# ADS1158.net
KiCad netlist of a schematic drawn in Altium Designer
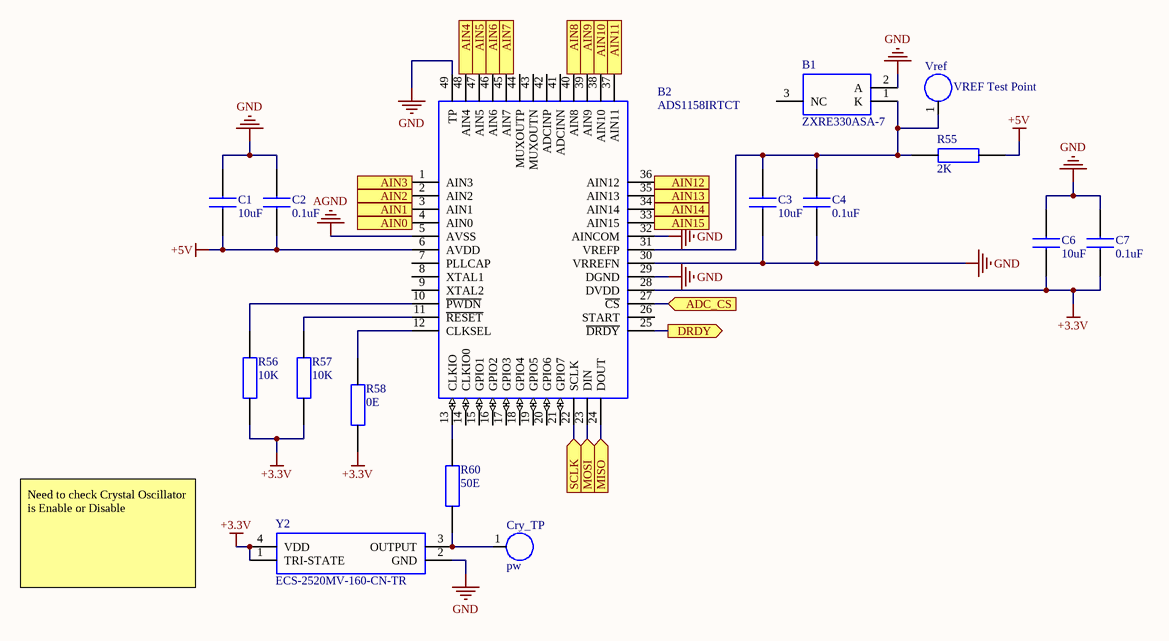
[diagram p0: ADS1158.SchDoc]

(export (version "E")
  (design (tool "Eeschema 10.0.6"))
  (components
    (comp (ref "B1")
      (value "ZXRE330ASA-7")
      (footprint "SOT96P240X110-3N")
      (description "Diodes Inc ZXRE330ASA-7, Shunt Precision Voltage Reference 3.3V, +/-0.5%, 3-Pin SOT-23")
      (fields (field (name "MOUSER PART NUMBER") "621-ZXRE330ASA-7"))
      (libsource (lib "ZXRE330ASA-7") (part "ZXRE330ASA-7"))
    )
    (comp (ref "B2")
      (value "ADS1158IRTCT")
      (footprint "QFN-48")
      (description "16-Bit, 125kSPS, 16-Ch Delta-Sigma ADC w/ Fast Channel Scan & Automatic Sequencer")
      (fields (field (name "MOUSER PART NUMBER") "595-ADS1158IRTCT"))
      (libsource (lib "ADS1158IRTCT") (part "ADS1158IRTCT"))
    )
    (comp (ref "C1")
      (value "10uF")
      (footprint "CAPC1608X80N")
      (description "TDK - C1608X5R1A106K080AC - CAP, MLCC, X5R, 10UF, 10V, 0603")
      (fields
        (field (name "MANUFACTURER_PART_NUMBER") "C1608X5R1A106K080AC")
        (field (name "MOUSER PART NUMBER") "810-C1608X5R1A106K")
      )
      (libsource (lib "10uF_0603") (part "C1608X5R1A106K080AC"))
    )
    (comp (ref "C2")
      (value "0.1uF")
      (footprint "CAPC1005X55N")
      (description "Multilayer Ceramic Capacitors MLCC - SMD/SMT 16V 0.1uF X7R 0402 20%")
      (fields
        (field (name "MANUFACTURER_PART_NUMBER") "C0402C104M4RECTU")
        (field (name "MOUSER PART NUMBER") "80-C0402C104M4RECTU")
      )
      (libsource (lib "0.1uF_0402") (part "C0402C104M4RECTU"))
    )
    (comp (ref "C3")
      (value "10uF")
      (footprint "CAPC1608X80N")
      (description "TDK - C1608X5R1A106K080AC - CAP, MLCC, X5R, 10UF, 10V, 0603")
      (fields
        (field (name "MANUFACTURER_PART_NUMBER") "C1608X5R1A106K080AC")
        (field (name "MOUSER PART NUMBER") "810-C1608X5R1A106K")
      )
      (libsource (lib "10uF_0603") (part "C1608X5R1A106K080AC"))
    )
    (comp (ref "C4")
      (value "0.1uF")
      (footprint "CAPC1005X55N")
      (description "Multilayer Ceramic Capacitors MLCC - SMD/SMT 16V 0.1uF X7R 0402 20%")
      (fields
        (field (name "MANUFACTURER_PART_NUMBER") "C0402C104M4RECTU")
        (field (name "MOUSER PART NUMBER") "80-C0402C104M4RECTU")
      )
      (libsource (lib "0.1uF_0402") (part "C0402C104M4RECTU"))
    )
    (comp (ref "C6")
      (value "10uF")
      (footprint "CAPC1608X80N")
      (description "TDK - C1608X5R1A106K080AC - CAP, MLCC, X5R, 10UF, 10V, 0603")
      (fields
        (field (name "MANUFACTURER_PART_NUMBER") "C1608X5R1A106K080AC")
        (field (name "MOUSER PART NUMBER") "810-C1608X5R1A106K")
      )
      (libsource (lib "10uF_0603") (part "C1608X5R1A106K080AC"))
    )
    (comp (ref "C7")
      (value "0.1uF")
      (footprint "CAPC1005X55N")
      (description "Multilayer Ceramic Capacitors MLCC - SMD/SMT 16V 0.1uF X7R 0402 20%")
      (fields
        (field (name "MANUFACTURER_PART_NUMBER") "C0402C104M4RECTU")
        (field (name "MOUSER PART NUMBER") "80-C0402C104M4RECTU")
      )
      (libsource (lib "0.1uF_0402") (part "C0402C104M4RECTU"))
    )
    (comp (ref "Cry_TP")
      (value "pw")
      (footprint "Test Points")
      (libsource (lib "CV-R-BAP_V2.1.5") (part "Test Points"))
    )
    (comp (ref "R55")
      (value "2K")
      (footprint "RESC1005X40N")
      (description "RESISTOR, 0402 2K Ohms +/-5% 1/16 W")
      (fields
        (field (name "MANUFACTURER_PART_NUMBER") "RC0402JR-072KL")
        (field (name "MOUSER PART NUMBER") "603-RC0402JR-072KL")
      )
      (libsource (lib "2K_0402") (part "RC0402JR-072KL"))
    )
    (comp (ref "R56")
      (value "10K")
      (footprint "RESC1005X40N")
      (fields
        (field (name "MANUFACTURER_PART_NUMBER") "CRCW040210K0FKED")
        (field (name "MOUSER PART NUMBER") "71-CRCW0402-10K-E3")
      )
      (libsource (lib "10K_0402") (part "CRCW040210K0FKED"))
    )
    (comp (ref "R57")
      (value "10K")
      (footprint "RESC1005X40N")
      (fields
        (field (name "MANUFACTURER_PART_NUMBER") "CRCW040210K0FKED")
        (field (name "MOUSER PART NUMBER") "71-CRCW0402-10K-E3")
      )
      (libsource (lib "10K_0402") (part "CRCW040210K0FKED"))
    )
    (comp (ref "R58")
      (value "0E")
      (footprint "RESC1005X40N")
      (description "Thick Film Resistors - SMD 0.0ohm 1%")
      (fields
        (field (name "MANUFACTURER_PART_NUMBER") "RC0402FR-070RL")
        (field (name "MOUSER PART NUMBER") "603-RC0402FR-070RL")
      )
      (libsource (lib "0E_0402") (part "RC0402FR-070RL"))
    )
    (comp (ref "R60")
      (value "50E")
      (footprint "RESC1005X35N")
      (description "Thin Film Resistors - SMD 50 ohm 0.1% 50 ppm High-Precision")
      (fields
        (field (name "MANUFACTURER_PART_NUMBER") "RT0402BRE0750RL")
        (field (name "MOUSER PART NUMBER") "603-RT0402BRE0750RL")
      )
      (libsource (lib "50E_0402") (part "RT0402BRE0750RL"))
    )
    (comp (ref "Vref")
      (value "VREF Test Point")
      (footprint "Test Points")
      (libsource (lib "CV-R-BAP_V2.1.5") (part "Test Points"))
    )
    (comp (ref "Y2")
      (value "ECS-2520MV-160-CN-TR")
      (footprint "ECS2520MV250BNTR")
      (description "Standard Clock Oscillators 16MHz 1.6-3.6 V 25ppm -40C +85C")
      (fields (field (name "MOUSER PART NUMBER") "520-2520MV-160-CNT"))
      (libsource (lib "16MHz_CO") (part "ECS-2520MV-160-CN-TR"))
    )
  )
  (nets
    (net (code "1") (name "+3.3V") (class "Default")
      (node (ref "B2") (pin "28") (pinfunction "DVDD_28") (pintype "power_in"))
      (node (ref "C6") (pin "1") (pinfunction "1_1") (pintype "passive"))
      (node (ref "C7") (pin "1") (pinfunction "1_1") (pintype "passive"))
      (node (ref "R56") (pin "1") (pinfunction "1_1") (pintype "passive"))
      (node (ref "R57") (pin "1") (pinfunction "1_1") (pintype "passive"))
      (node (ref "R58") (pin "1") (pinfunction "1_1") (pintype "passive"))
      (node (ref "Y2") (pin "1") (pinfunction "TRI-STATE_1") (pintype "passive"))
      (node (ref "Y2") (pin "4") (pinfunction "VDD_4") (pintype "passive"))
    )
    (net (code "2") (name "+5V") (class "Default")
      (node (ref "B2") (pin "6") (pinfunction "AVDD_6") (pintype "power_in"))
      (node (ref "C1") (pin "1") (pinfunction "1_1") (pintype "passive"))
      (node (ref "C2") (pin "1") (pinfunction "1_1") (pintype "passive"))
      (node (ref "R55") (pin "2") (pinfunction "2_2") (pintype "passive"))
    )
    (net (code "3") (name "/ADC_CS") (class "Default")
      (node (ref "B2") (pin "27") (pinfunction "CS_27") (pintype "passive"))
    )
    (net (code "4") (name "/AIN0") (class "Default")
      (node (ref "B2") (pin "4") (pinfunction "AIN0_4") (pintype "passive"))
    )
    (net (code "5") (name "/AIN1") (class "Default")
      (node (ref "B2") (pin "3") (pinfunction "AIN1_3") (pintype "passive"))
    )
    (net (code "6") (name "/AIN2") (class "Default")
      (node (ref "B2") (pin "2") (pinfunction "AIN2_2") (pintype "passive"))
    )
    (net (code "7") (name "/AIN3") (class "Default")
      (node (ref "B2") (pin "1") (pinfunction "AIN3_1") (pintype "passive"))
    )
    (net (code "8") (name "/AIN4") (class "Default")
      (node (ref "B2") (pin "48") (pinfunction "AIN4_48") (pintype "passive"))
    )
    (net (code "9") (name "/AIN5") (class "Default")
      (node (ref "B2") (pin "47") (pinfunction "AIN5_47") (pintype "passive"))
    )
    (net (code "10") (name "/AIN6") (class "Default")
      (node (ref "B2") (pin "46") (pinfunction "AIN6_46") (pintype "passive"))
    )
    (net (code "11") (name "/AIN7") (class "Default")
      (node (ref "B2") (pin "45") (pinfunction "AIN7_45") (pintype "passive"))
    )
    (net (code "12") (name "/AIN8") (class "Default")
      (node (ref "B2") (pin "40") (pinfunction "AIN8_40") (pintype "passive"))
    )
    (net (code "13") (name "/AIN9") (class "Default")
      (node (ref "B2") (pin "39") (pinfunction "AIN9_39") (pintype "passive"))
    )
    (net (code "14") (name "/AIN10") (class "Default")
      (node (ref "B2") (pin "38") (pinfunction "AIN10_38") (pintype "passive"))
    )
    (net (code "15") (name "/AIN11") (class "Default")
      (node (ref "B2") (pin "37") (pinfunction "AIN11_37") (pintype "passive"))
    )
    (net (code "16") (name "/AIN12") (class "Default")
      (node (ref "B2") (pin "36") (pinfunction "AIN12_36") (pintype "passive"))
    )
    (net (code "17") (name "/AIN13") (class "Default")
      (node (ref "B2") (pin "35") (pinfunction "AIN13_35") (pintype "passive"))
    )
    (net (code "18") (name "/AIN14") (class "Default")
      (node (ref "B2") (pin "34") (pinfunction "AIN14_34") (pintype "passive"))
    )
    (net (code "19") (name "/AIN15") (class "Default")
      (node (ref "B2") (pin "33") (pinfunction "AIN15_33") (pintype "passive"))
    )
    (net (code "20") (name "/DRDY") (class "Default")
      (node (ref "B2") (pin "25") (pinfunction "DRDY_25") (pintype "passive"))
    )
    (net (code "21") (name "/MISO") (class "Default")
      (node (ref "B2") (pin "24") (pinfunction "DOUT_24") (pintype "passive"))
    )
    (net (code "22") (name "/MOSI") (class "Default")
      (node (ref "B2") (pin "23") (pinfunction "DIN_23") (pintype "passive"))
    )
    (net (code "23") (name "/SCLK") (class "Default")
      (node (ref "B2") (pin "22") (pinfunction "SCLK_22") (pintype "passive"))
    )
    (net (code "24") (name "AGND") (class "Default")
      (node (ref "B2") (pin "5") (pinfunction "AVSS_5") (pintype "passive"))
    )
    (net (code "25") (name "GND") (class "Default")
      (node (ref "B1") (pin "2") (pinfunction "A_2") (pintype "passive"))
      (node (ref "B2") (pin "29") (pinfunction "DGND_29") (pintype "passive"))
      (node (ref "B2") (pin "30") (pinfunction "VRREFN_30") (pintype "passive"))
      (node (ref "B2") (pin "32") (pinfunction "AINCOM_32") (pintype "passive"))
      (node (ref "B2") (pin "49") (pinfunction "TP_49") (pintype "passive"))
      (node (ref "C1") (pin "2") (pinfunction "2_2") (pintype "passive"))
      (node (ref "C2") (pin "2") (pinfunction "2_2") (pintype "passive"))
      (node (ref "C3") (pin "1") (pinfunction "1_1") (pintype "passive"))
      (node (ref "C4") (pin "1") (pinfunction "1_1") (pintype "passive"))
      (node (ref "C6") (pin "2") (pinfunction "2_2") (pintype "passive"))
      (node (ref "C7") (pin "2") (pinfunction "2_2") (pintype "passive"))
      (node (ref "Y2") (pin "2") (pinfunction "GND_2") (pintype "passive"))
    )
    (net (code "26") (name "Net-(B1-K)") (class "Default")
      (node (ref "B1") (pin "1") (pinfunction "K_1") (pintype "passive"))
      (node (ref "B2") (pin "31") (pinfunction "VREFP_31") (pintype "passive"))
      (node (ref "C3") (pin "2") (pinfunction "2_2") (pintype "passive"))
      (node (ref "C4") (pin "2") (pinfunction "2_2") (pintype "passive"))
      (node (ref "R55") (pin "1") (pinfunction "1_1") (pintype "passive"))
      (node (ref "Vref") (pin "1") (pinfunction "1_1") (pintype "passive"))
    )
    (net (code "27") (name "Net-(B2-CLKIO)") (class "Default")
      (node (ref "B2") (pin "13") (pinfunction "CLKIO_13") (pintype "bidirectional"))
      (node (ref "R60") (pin "2") (pinfunction "2_2") (pintype "passive"))
    )
    (net (code "28") (name "Net-(B2-CLKSEL)") (class "Default")
      (node (ref "B2") (pin "12") (pinfunction "CLKSEL_12") (pintype "passive"))
      (node (ref "R58") (pin "2") (pinfunction "2_2") (pintype "passive"))
    )
    (net (code "29") (name "Net-(B2-PWDN)") (class "Default")
      (node (ref "B2") (pin "10") (pinfunction "PWDN_10") (pintype "passive"))
      (node (ref "R56") (pin "2") (pinfunction "2_2") (pintype "passive"))
    )
    (net (code "30") (name "Net-(B2-RESET)") (class "Default")
      (node (ref "B2") (pin "11") (pinfunction "RESET_11") (pintype "passive"))
      (node (ref "R57") (pin "2") (pinfunction "2_2") (pintype "passive"))
    )
    (net (code "31") (name "Net-(Y2-OUTPUT)") (class "Default")
      (node (ref "Cry_TP") (pin "1") (pinfunction "1_1") (pintype "passive"))
      (node (ref "R60") (pin "1") (pinfunction "1_1") (pintype "passive"))
      (node (ref "Y2") (pin "3") (pinfunction "OUTPUT_3") (pintype "passive"))
    )
    (net (code "32") (name "unconnected-(B1-NC-Pad3)") (class "Default")
      (node (ref "B1") (pin "3") (pinfunction "NC_3") (pintype "passive"))
    )
    (net (code "33") (name "unconnected-(B2-ADCINN-Pad41)") (class "Default")
      (node (ref "B2") (pin "41") (pinfunction "ADCINN_41") (pintype "passive"))
    )
    (net (code "34") (name "unconnected-(B2-ADCINP-Pad42)") (class "Default")
      (node (ref "B2") (pin "42") (pinfunction "ADCINP_42") (pintype "passive"))
    )
    (net (code "35") (name "unconnected-(B2-CLKIO0-Pad14)") (class "Default")
      (node (ref "B2") (pin "14") (pinfunction "CLKIO0_14") (pintype "bidirectional"))
    )
    (net (code "36") (name "unconnected-(B2-GPIO1-Pad15)") (class "Default")
      (node (ref "B2") (pin "15") (pinfunction "GPIO1_15") (pintype "bidirectional"))
    )
    (net (code "37") (name "unconnected-(B2-GPIO2-Pad16)") (class "Default")
      (node (ref "B2") (pin "16") (pinfunction "GPIO2_16") (pintype "bidirectional"))
    )
    (net (code "38") (name "unconnected-(B2-GPIO3-Pad17)") (class "Default")
      (node (ref "B2") (pin "17") (pinfunction "GPIO3_17") (pintype "bidirectional"))
    )
    (net (code "39") (name "unconnected-(B2-GPIO4-Pad18)") (class "Default")
      (node (ref "B2") (pin "18") (pinfunction "GPIO4_18") (pintype "bidirectional"))
    )
    (net (code "40") (name "unconnected-(B2-GPIO5-Pad19)") (class "Default")
      (node (ref "B2") (pin "19") (pinfunction "GPIO5_19") (pintype "bidirectional"))
    )
    (net (code "41") (name "unconnected-(B2-GPIO6-Pad20)") (class "Default")
      (node (ref "B2") (pin "20") (pinfunction "GPIO6_20") (pintype "bidirectional"))
    )
    (net (code "42") (name "unconnected-(B2-GPIO7-Pad21)") (class "Default")
      (node (ref "B2") (pin "21") (pinfunction "GPIO7_21") (pintype "bidirectional"))
    )
    (net (code "43") (name "unconnected-(B2-MUXOUTN-Pad43)") (class "Default")
      (node (ref "B2") (pin "43") (pinfunction "MUXOUTN_43") (pintype "passive"))
    )
    (net (code "44") (name "unconnected-(B2-MUXOUTP-Pad44)") (class "Default")
      (node (ref "B2") (pin "44") (pinfunction "MUXOUTP_44") (pintype "passive"))
    )
    (net (code "45") (name "unconnected-(B2-PLLCAP-Pad7)") (class "Default")
      (node (ref "B2") (pin "7") (pinfunction "PLLCAP_7") (pintype "passive"))
    )
    (net (code "46") (name "unconnected-(B2-START-Pad26)") (class "Default")
      (node (ref "B2") (pin "26") (pinfunction "START_26") (pintype "passive"))
    )
    (net (code "47") (name "unconnected-(B2-XTAL1-Pad8)") (class "Default")
      (node (ref "B2") (pin "8") (pinfunction "XTAL1_8") (pintype "passive"))
    )
    (net (code "48") (name "unconnected-(B2-XTAL2-Pad9)") (class "Default")
      (node (ref "B2") (pin "9") (pinfunction "XTAL2_9") (pintype "passive"))
    )
  )
)
